# MCU.net
KiCad netlist of a schematic drawn in Altium Designer
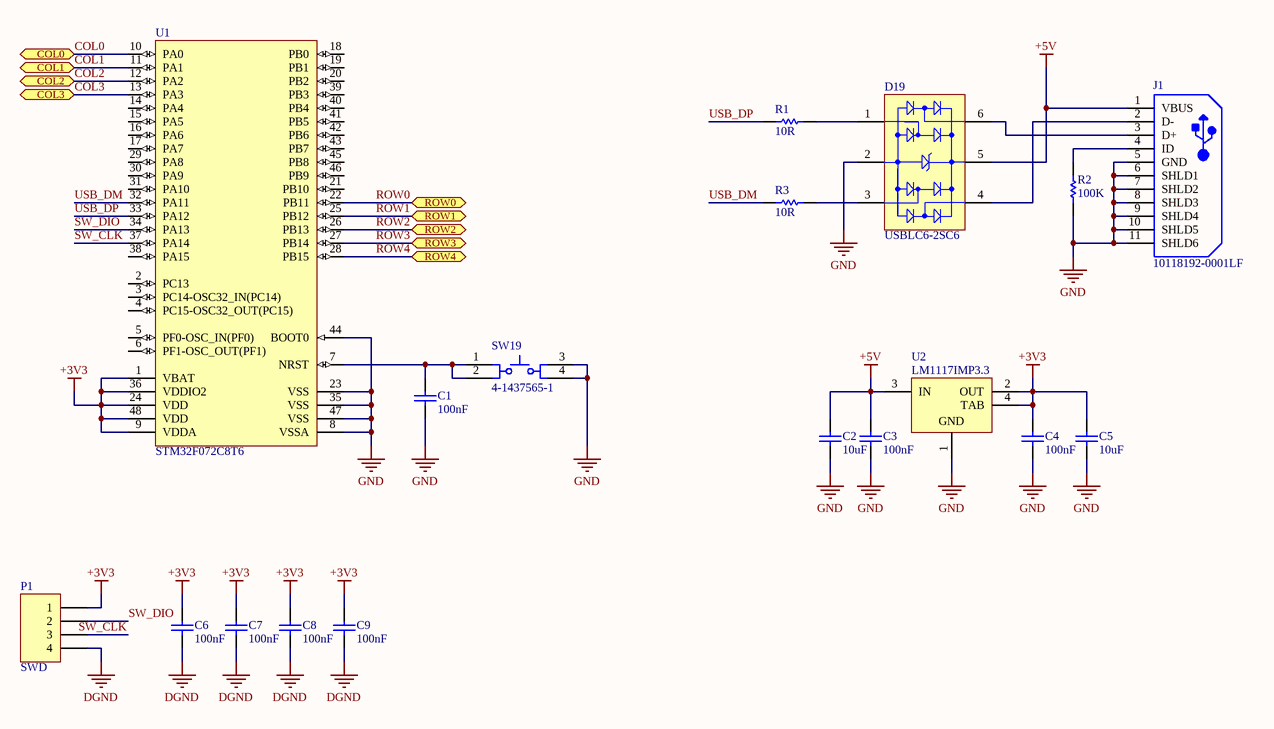
[diagram p0: MCU.SchDoc]

(export (version "E")
  (design (tool "Eeschema 10.0.6"))
  (components
    (comp (ref "C1")
      (value "100nF")
      (footprint "CAPC0603(1608)100_M")
      (description "CAP 100nF 25V -20% to +80% 0603 (1608 Metric) Thickness 1mm SMD")
      (fields (field (name "TOLERANCE") "-20% to +80%"))
      (libsource (lib "Altium Content Vault") (part "CAP"))
    )
    (comp (ref "C2")
      (value "10uF")
      (footprint "CAPC1206(3216)190_L")
      (description "CAP 10uF 16V ±10% 1206 (3216 Metric) Thickness 1.9mm SMD")
      (fields (field (name "TOLERANCE") "Â±10%"))
      (libsource (lib "Altium Content Vault") (part "CAP"))
    )
    (comp (ref "C3")
      (value "100nF")
      (footprint "CAPC0603(1608)100_M")
      (description "CAP 100nF 25V -20% to +80% 0603 (1608 Metric) Thickness 1mm SMD")
      (fields (field (name "TOLERANCE") "-20% to +80%"))
      (libsource (lib "Altium Content Vault") (part "CAP"))
    )
    (comp (ref "C4")
      (value "100nF")
      (footprint "CAPC0603(1608)100_M")
      (description "CAP 100nF 25V -20% to +80% 0603 (1608 Metric) Thickness 1mm SMD")
      (fields (field (name "TOLERANCE") "-20% to +80%"))
      (libsource (lib "Altium Content Vault") (part "CAP"))
    )
    (comp (ref "C5")
      (value "10uF")
      (footprint "CAPC1206(3216)190_L")
      (description "CAP 10uF 16V ±10% 1206 (3216 Metric) Thickness 1.9mm SMD")
      (fields (field (name "TOLERANCE") "Â±10%"))
      (libsource (lib "Altium Content Vault") (part "CAP"))
    )
    (comp (ref "C6")
      (value "100nF")
      (footprint "CAPC0603(1608)100_M")
      (description "CAP 100nF 25V -20% to +80% 0603 (1608 Metric) Thickness 1mm SMD")
      (fields (field (name "TOLERANCE") "-20% to +80%"))
      (libsource (lib "Altium Content Vault") (part "CAP"))
    )
    (comp (ref "C7")
      (value "100nF")
      (footprint "CAPC0603(1608)100_M")
      (description "CAP 100nF 25V -20% to +80% 0603 (1608 Metric) Thickness 1mm SMD")
      (fields (field (name "TOLERANCE") "-20% to +80%"))
      (libsource (lib "Altium Content Vault") (part "CAP"))
    )
    (comp (ref "C8")
      (value "100nF")
      (footprint "CAPC0603(1608)100_M")
      (description "CAP 100nF 25V -20% to +80% 0603 (1608 Metric) Thickness 1mm SMD")
      (fields (field (name "TOLERANCE") "-20% to +80%"))
      (libsource (lib "Altium Content Vault") (part "CAP"))
    )
    (comp (ref "C9")
      (value "100nF")
      (footprint "CAPC0603(1608)100_M")
      (description "CAP 100nF 25V -20% to +80% 0603 (1608 Metric) Thickness 1mm SMD")
      (fields (field (name "TOLERANCE") "-20% to +80%"))
      (libsource (lib "Altium Content Vault") (part "CAP"))
    )
    (comp (ref "D19")
      (value "USBLC6-2SC6")
      (footprint "STM-SOT23-6L_V")
      (description "Very low capacitance ESD protection, 3.5 pF, -40 to 125 degC, 6-Pin SOT23, RoHS, Tape and Reel")
      (fields (field (name "MANUFACTURER") "STMicroelectronics"))
      (libsource (lib "Altium Content Vault") (part "STM-USB_DVI_HDMIULC6-4SC6X-SOT23-6L"))
    )
    (comp (ref "J1")
      (value "10118192-0001LF")
      (footprint "FCI-10118192-0001LF-5_V")
      (description "Micro USB B Type Receptacle, -55 to 85 degC, 5-Pin SMD, RoHS, Tape and Reel")
      (fields (field (name "MANUFACTURER") "FCI"))
      (libsource (lib "Altium Content Vault") (part "USB-5-6SHLD"))
    )
    (comp (ref "P1")
      (value "SWD")
      (footprint "HDR1X4H")
      (description "Header, 4-Pin, Right Angle")
      (fields (field (name "PUBLISHER") "Altium Limited"))
      (libsource (lib "Miscellaneous Connectors") (part "Header 4H"))
    )
    (comp (ref "R1")
      (value "10R")
      (footprint "RESC0603(1608)_L")
      (description "10R 0.1W 1% 0603 (1608 Metric)  SMD")
      (fields (field (name "TOLERANCE") "1 %") (field (name "POWER") "0.1 W"))
      (libsource (lib "Altium Content Vault") (part "RES"))
    )
    (comp (ref "R2")
      (value "100K")
      (footprint "RESC0603(1608)_N")
      (description "100K 0.1W 1% 0603 (1608 Metric)  SMD")
      (fields (field (name "POWER") "0.1 W") (field (name "TOLERANCE") "1 %"))
      (libsource (lib "Altium Content Vault") (part "RES"))
    )
    (comp (ref "R3")
      (value "10R")
      (footprint "RESC0603(1608)_L")
      (description "10R 0.1W 1% 0603 (1608 Metric)  SMD")
      (fields (field (name "TOLERANCE") "1 %") (field (name "POWER") "0.1 W"))
      (libsource (lib "Altium Content Vault") (part "RES"))
    )
    (comp (ref "SW19")
      (value "4-1437565-1")
      (footprint "TECO-4-1437565-1_V")
      (description "Tactile Switch, 50 mA, 12 VDC, -20 to 85 degC, 4-Pin SMD, RoHS, Bulk")
      (fields (field (name "MANUFACTURER") "TEConnectivity/AMPBrand"))
      (libsource (lib "Altium Content Vault") (part "SW-SPST-NO-4"))
    )
    (comp (ref "U1")
      (value "STM32F072C8T6")
      (footprint "STM-LQFP48_M")
      (fields (field (name "MANUFACTURER") "STMicroelectronics"))
      (libsource (lib "Altium Content Vault") (part "MC-ARM-STM32F07X-LQFP48"))
    )
    (comp (ref "U2")
      (value "LM1117IMP3.3")
      (footprint "DCY0004A_N")
      (description "800mA Low-Dropout Linear Regulator, 4-pin SOT-223, Pb-Free")
      (fields
        (field (name "PARTNUMBER") "LM1117IMP-3.3/NOPB")
        (field (name "MANUFACTURER") "Texas Instruments")
      )
      (libsource (lib "Altium Content Vault") (part "PM-REG-LM1086-SOT4"))
    )
  )
  (nets
    (net (code "1") (name "+3V3") (class "Default")
      (node (ref "C4") (pin "2") (pinfunction "2_2") (pintype "passive"))
      (node (ref "C5") (pin "2") (pinfunction "2_2") (pintype "passive"))
      (node (ref "C6") (pin "2") (pinfunction "2_2") (pintype "passive"))
      (node (ref "C7") (pin "2") (pinfunction "2_2") (pintype "passive"))
      (node (ref "C8") (pin "2") (pinfunction "2_2") (pintype "passive"))
      (node (ref "C9") (pin "2") (pinfunction "2_2") (pintype "passive"))
      (node (ref "P1") (pin "1") (pinfunction "1_1") (pintype "passive"))
      (node (ref "U1") (pin "1") (pinfunction "VBAT_1") (pintype "power_in"))
      (node (ref "U1") (pin "24") (pinfunction "VDD_24") (pintype "power_in"))
      (node (ref "U1") (pin "36") (pinfunction "VDDIO2_36") (pintype "power_in"))
      (node (ref "U1") (pin "48") (pinfunction "VDD_48") (pintype "power_in"))
      (node (ref "U1") (pin "9") (pinfunction "VDDA_9") (pintype "power_in"))
      (node (ref "U2") (pin "2") (pinfunction "OUT_2") (pintype "power_in"))
      (node (ref "U2") (pin "4") (pinfunction "TAB_4") (pintype "power_in"))
    )
    (net (code "2") (name "+5V") (class "Default")
      (node (ref "C2") (pin "2") (pinfunction "2_2") (pintype "passive"))
      (node (ref "C3") (pin "2") (pinfunction "2_2") (pintype "passive"))
      (node (ref "D19") (pin "5") (pinfunction "VBUS_5") (pintype "passive"))
      (node (ref "J1") (pin "1") (pinfunction "VBUS_1") (pintype "passive"))
      (node (ref "U2") (pin "3") (pinfunction "IN_3") (pintype "power_in"))
    )
    (net (code "3") (name "/COL0") (class "Default")
      (node (ref "U1") (pin "10") (pinfunction "PA0_10") (pintype "bidirectional"))
    )
    (net (code "4") (name "/COL1") (class "Default")
      (node (ref "U1") (pin "11") (pinfunction "PA1_11") (pintype "bidirectional"))
    )
    (net (code "5") (name "/COL2") (class "Default")
      (node (ref "U1") (pin "12") (pinfunction "PA2_12") (pintype "bidirectional"))
    )
    (net (code "6") (name "/COL3") (class "Default")
      (node (ref "U1") (pin "13") (pinfunction "PA3_13") (pintype "bidirectional"))
    )
    (net (code "7") (name "/ROW0") (class "Default")
      (node (ref "U1") (pin "22") (pinfunction "PB11_22") (pintype "bidirectional"))
    )
    (net (code "8") (name "/ROW1") (class "Default")
      (node (ref "U1") (pin "25") (pinfunction "PB12_25") (pintype "bidirectional"))
    )
    (net (code "9") (name "/ROW2") (class "Default")
      (node (ref "U1") (pin "26") (pinfunction "PB13_26") (pintype "bidirectional"))
    )
    (net (code "10") (name "/ROW3") (class "Default")
      (node (ref "U1") (pin "27") (pinfunction "PB14_27") (pintype "bidirectional"))
    )
    (net (code "11") (name "/ROW4") (class "Default")
      (node (ref "U1") (pin "28") (pinfunction "PB15_28") (pintype "bidirectional"))
    )
    (net (code "12") (name "/SW_CLK") (class "Default")
      (node (ref "P1") (pin "3") (pinfunction "3_3") (pintype "passive"))
      (node (ref "U1") (pin "37") (pinfunction "PA14_37") (pintype "bidirectional"))
    )
    (net (code "13") (name "/SW_DIO") (class "Default")
      (node (ref "P1") (pin "2") (pinfunction "2_2") (pintype "passive"))
      (node (ref "U1") (pin "34") (pinfunction "PA13_34") (pintype "bidirectional"))
    )
    (net (code "14") (name "/USB_DM") (class "Default")
      (node (ref "R3") (pin "1") (pinfunction "1_1") (pintype "passive"))
      (node (ref "U1") (pin "32") (pinfunction "PA11_32") (pintype "bidirectional"))
    )
    (net (code "15") (name "/USB_DP") (class "Default")
      (node (ref "R1") (pin "1") (pinfunction "1_1") (pintype "passive"))
      (node (ref "U1") (pin "33") (pinfunction "PA12_33") (pintype "bidirectional"))
    )
    (net (code "16") (name "DGND") (class "Default")
      (node (ref "C6") (pin "1") (pinfunction "1_1") (pintype "passive"))
      (node (ref "C7") (pin "1") (pinfunction "1_1") (pintype "passive"))
      (node (ref "C8") (pin "1") (pinfunction "1_1") (pintype "passive"))
      (node (ref "C9") (pin "1") (pinfunction "1_1") (pintype "passive"))
      (node (ref "P1") (pin "4") (pinfunction "4_4") (pintype "passive"))
    )
    (net (code "17") (name "GND") (class "Default")
      (node (ref "C1") (pin "1") (pinfunction "1_1") (pintype "passive"))
      (node (ref "C2") (pin "1") (pinfunction "1_1") (pintype "passive"))
      (node (ref "C3") (pin "1") (pinfunction "1_1") (pintype "passive"))
      (node (ref "C4") (pin "1") (pinfunction "1_1") (pintype "passive"))
      (node (ref "C5") (pin "1") (pinfunction "1_1") (pintype "passive"))
      (node (ref "D19") (pin "2") (pinfunction "GND_2") (pintype "passive"))
      (node (ref "J1") (pin "10") (pinfunction "SHLD5_10") (pintype "passive"))
      (node (ref "J1") (pin "11") (pinfunction "SHLD6_11") (pintype "passive"))
      (node (ref "J1") (pin "5") (pinfunction "GND_5") (pintype "passive"))
      (node (ref "J1") (pin "6") (pinfunction "SHLD1_6") (pintype "passive"))
      (node (ref "J1") (pin "7") (pinfunction "SHLD2_7") (pintype "passive"))
      (node (ref "J1") (pin "8") (pinfunction "SHLD3_8") (pintype "passive"))
      (node (ref "J1") (pin "9") (pinfunction "SHLD4_9") (pintype "passive"))
      (node (ref "R2") (pin "1") (pinfunction "1_1") (pintype "passive"))
      (node (ref "SW19") (pin "3") (pinfunction "3_3") (pintype "passive"))
      (node (ref "SW19") (pin "4") (pinfunction "4_4") (pintype "passive"))
      (node (ref "U1") (pin "23") (pinfunction "VSS_23") (pintype "power_in"))
      (node (ref "U1") (pin "35") (pinfunction "VSS_35") (pintype "power_in"))
      (node (ref "U1") (pin "44") (pinfunction "BOOT0_44") (pintype "input"))
      (node (ref "U1") (pin "47") (pinfunction "VSS_47") (pintype "power_in"))
      (node (ref "U1") (pin "8") (pinfunction "VSSA_8") (pintype "power_in"))
      (node (ref "U2") (pin "1") (pinfunction "GND_1") (pintype "power_in"))
    )
    (net (code "18") (name "Net-(D19-I{slash}O_1)") (class "Default")
      (node (ref "D19") (pin "1") (pinfunction "I/O_1_1") (pintype "passive"))
      (node (ref "R1") (pin "2") (pinfunction "2_2") (pintype "passive"))
    )
    (net (code "19") (name "Net-(D19-I{slash}O_2)") (class "Default")
      (node (ref "D19") (pin "3") (pinfunction "I/O_2_3") (pintype "passive"))
      (node (ref "R3") (pin "2") (pinfunction "2_2") (pintype "passive"))
    )
    (net (code "20") (name "Net-(D19-I{slash}O_3)") (class "Default")
      (node (ref "D19") (pin "4") (pinfunction "I/O_3_4") (pintype "passive"))
      (node (ref "J1") (pin "2") (pinfunction "D-_2") (pintype "passive"))
    )
    (net (code "21") (name "Net-(D19-I{slash}O_4)") (class "Default")
      (node (ref "D19") (pin "6") (pinfunction "I/O_4_6") (pintype "passive"))
      (node (ref "J1") (pin "3") (pinfunction "D+_3") (pintype "passive"))
    )
    (net (code "22") (name "Net-(J1-ID)") (class "Default")
      (node (ref "J1") (pin "4") (pinfunction "ID_4") (pintype "passive"))
      (node (ref "R2") (pin "2") (pinfunction "2_2") (pintype "passive"))
    )
    (net (code "23") (name "Net-(U1-NRST)") (class "Default")
      (node (ref "C1") (pin "2") (pinfunction "2_2") (pintype "passive"))
      (node (ref "SW19") (pin "1") (pinfunction "1_1") (pintype "passive"))
      (node (ref "SW19") (pin "2") (pinfunction "2_2") (pintype "passive"))
      (node (ref "U1") (pin "7") (pinfunction "NRST_7") (pintype "bidirectional"))
    )
    (net (code "24") (name "unconnected-(U1-PA4-Pad14)") (class "Default")
      (node (ref "U1") (pin "14") (pinfunction "PA4_14") (pintype "bidirectional"))
    )
    (net (code "25") (name "unconnected-(U1-PA5-Pad15)") (class "Default")
      (node (ref "U1") (pin "15") (pinfunction "PA5_15") (pintype "bidirectional"))
    )
    (net (code "26") (name "unconnected-(U1-PA6-Pad16)") (class "Default")
      (node (ref "U1") (pin "16") (pinfunction "PA6_16") (pintype "bidirectional"))
    )
    (net (code "27") (name "unconnected-(U1-PA7-Pad17)") (class "Default")
      (node (ref "U1") (pin "17") (pinfunction "PA7_17") (pintype "bidirectional"))
    )
    (net (code "28") (name "unconnected-(U1-PA8-Pad29)") (class "Default")
      (node (ref "U1") (pin "29") (pinfunction "PA8_29") (pintype "bidirectional"))
    )
    (net (code "29") (name "unconnected-(U1-PA9-Pad30)") (class "Default")
      (node (ref "U1") (pin "30") (pinfunction "PA9_30") (pintype "bidirectional"))
    )
    (net (code "30") (name "unconnected-(U1-PA10-Pad31)") (class "Default")
      (node (ref "U1") (pin "31") (pinfunction "PA10_31") (pintype "bidirectional"))
    )
    (net (code "31") (name "unconnected-(U1-PA15-Pad38)") (class "Default")
      (node (ref "U1") (pin "38") (pinfunction "PA15_38") (pintype "bidirectional"))
    )
    (net (code "32") (name "unconnected-(U1-PB0-Pad18)") (class "Default")
      (node (ref "U1") (pin "18") (pinfunction "PB0_18") (pintype "bidirectional"))
    )
    (net (code "33") (name "unconnected-(U1-PB1-Pad19)") (class "Default")
      (node (ref "U1") (pin "19") (pinfunction "PB1_19") (pintype "bidirectional"))
    )
    (net (code "34") (name "unconnected-(U1-PB2-Pad20)") (class "Default")
      (node (ref "U1") (pin "20") (pinfunction "PB2_20") (pintype "bidirectional"))
    )
    (net (code "35") (name "unconnected-(U1-PB3-Pad39)") (class "Default")
      (node (ref "U1") (pin "39") (pinfunction "PB3_39") (pintype "bidirectional"))
    )
    (net (code "36") (name "unconnected-(U1-PB4-Pad40)") (class "Default")
      (node (ref "U1") (pin "40") (pinfunction "PB4_40") (pintype "bidirectional"))
    )
    (net (code "37") (name "unconnected-(U1-PB5-Pad41)") (class "Default")
      (node (ref "U1") (pin "41") (pinfunction "PB5_41") (pintype "bidirectional"))
    )
    (net (code "38") (name "unconnected-(U1-PB6-Pad42)") (class "Default")
      (node (ref "U1") (pin "42") (pinfunction "PB6_42") (pintype "bidirectional"))
    )
    (net (code "39") (name "unconnected-(U1-PB7-Pad43)") (class "Default")
      (node (ref "U1") (pin "43") (pinfunction "PB7_43") (pintype "bidirectional"))
    )
    (net (code "40") (name "unconnected-(U1-PB8-Pad45)") (class "Default")
      (node (ref "U1") (pin "45") (pinfunction "PB8_45") (pintype "bidirectional"))
    )
    (net (code "41") (name "unconnected-(U1-PB9-Pad46)") (class "Default")
      (node (ref "U1") (pin "46") (pinfunction "PB9_46") (pintype "bidirectional"))
    )
    (net (code "42") (name "unconnected-(U1-PB10-Pad21)") (class "Default")
      (node (ref "U1") (pin "21") (pinfunction "PB10_21") (pintype "bidirectional"))
    )
    (net (code "43") (name "unconnected-(U1-PC13-Pad2)") (class "Default")
      (node (ref "U1") (pin "2") (pinfunction "PC13_2") (pintype "bidirectional"))
    )
    (net (code "44") (name "unconnected-(U1-PC14-OSC32_IN(PC14)-Pad3)") (class "Default")
      (node (ref "U1") (pin "3") (pinfunction "PC14-OSC32_IN(PC14)_3") (pintype "bidirectional"))
    )
    (net (code "45") (name "unconnected-(U1-PC15-OSC32_OUT(PC15)-Pad4)") (class "Default")
      (node (ref "U1") (pin "4") (pinfunction "PC15-OSC32_OUT(PC15)_4") (pintype "bidirectional"))
    )
    (net (code "46") (name "unconnected-(U1-PF0-OSC_IN(PF0)-Pad5)") (class "Default")
      (node (ref "U1") (pin "5") (pinfunction "PF0-OSC_IN(PF0)_5") (pintype "bidirectional"))
    )
    (net (code "47") (name "unconnected-(U1-PF1-OSC_OUT(PF1)-Pad6)") (class "Default")
      (node (ref "U1") (pin "6") (pinfunction "PF1-OSC_OUT(PF1)_6") (pintype "bidirectional"))
    )
  )
)
